# Large_Digit_Shield.net
KiCad netlist of a schematic drawn in EAGLE
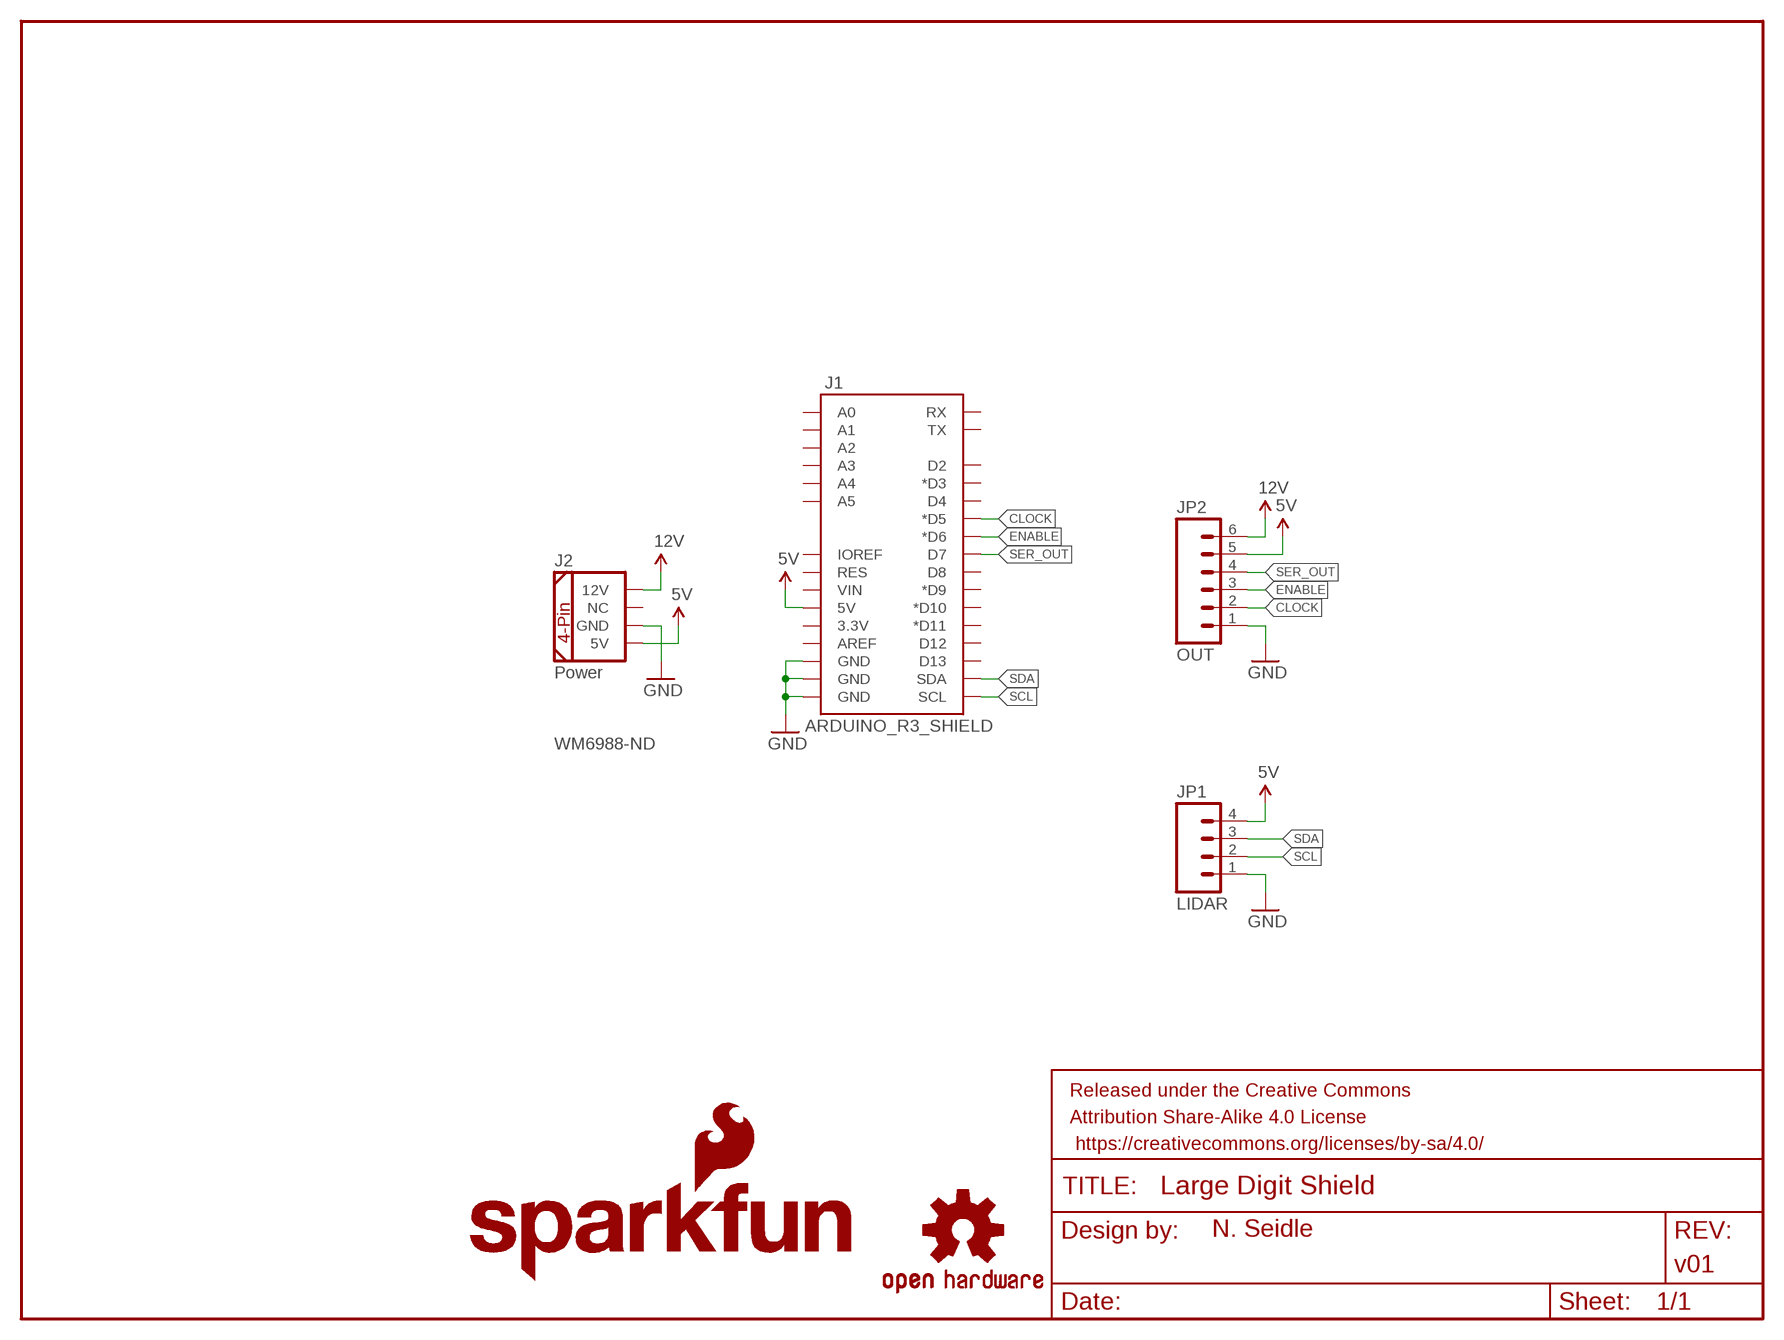
[diagram p0: schematic, sheet 1]

(export (version "E")
  (design (tool "Eeschema 10.0.6"))
  (components
    (comp (ref "FRAME1")
      (value "FRAME-LETTER")
      (footprint "eagle-import:CREATIVE_COMMONS")
      (fields (field (name "DESIGNER") "N. Seidle"))
      (libsource (lib "eagle-import") (part "FRAME-LETTER"))
    )
    (comp (ref "J1")
      (value "ARDUINO_R3_SHIELD")
      (footprint "eagle-import:UNO_R3_SHIELD")
      (libsource (lib "eagle-import") (part "ARDUINO_R3_SHIELD"))
    )
    (comp (ref "J2")
      (value "Power")
      (footprint "eagle-import:COMPUTER-PERIPHERAL-POWER-RA")
      (libsource (lib "eagle-import") (part "COMPUTER-PERIPHERAL-POWERRA"))
    )
    (comp (ref "JP1")
      (value "LIDAR")
      (footprint "eagle-import:JST-4-PTH")
      (libsource (lib "eagle-import") (part "M04JST-PTH"))
    )
    (comp (ref "JP2")
      (value "OUT")
      (footprint "eagle-import:1X06")
      (libsource (lib "eagle-import") (part "M06SILK_FEMALE_PTH"))
    )
    (comp (ref "LOGO1")
      (value "SFE_LOGO_NAME_FLAME.2_INCH")
      (footprint "eagle-import:SFE_LOGO_NAME_FLAME_.2")
      (libsource (lib "eagle-import") (part "SFE_LOGO_NAME_FLAME.2_INCH"))
    )
    (comp (ref "LOGO2")
      (value "OSHW-LOGOS")
      (footprint "eagle-import:OSHW-LOGO-S")
      (libsource (lib "eagle-import") (part "OSHW-LOGOS"))
    )
  )
  (nets
    (net (code "1") (name "5V") (class "Default")
      (node (ref "J1") (pin "5V") (pinfunction "5V_5V") (pintype "bidirectional"))
      (node (ref "J2") (pin "5V") (pinfunction "5V_5V") (pintype "passive"))
      (node (ref "JP1") (pin "4") (pinfunction "4_4") (pintype "passive"))
      (node (ref "JP2") (pin "5") (pinfunction "5_5") (pintype "passive"))
    )
    (net (code "2") (name "12V") (class "Default")
      (node (ref "J2") (pin "12V") (pinfunction "12V_12V") (pintype "passive"))
      (node (ref "JP2") (pin "6") (pinfunction "6_6") (pintype "passive"))
    )
    (net (code "3") (name "CLOCK") (class "Default")
      (node (ref "J1") (pin "D5") (pinfunction "*D5_D5") (pintype "bidirectional"))
      (node (ref "JP2") (pin "2") (pinfunction "2_2") (pintype "passive"))
    )
    (net (code "4") (name "ENABLE") (class "Default")
      (node (ref "J1") (pin "D6") (pinfunction "*D6_D6") (pintype "bidirectional"))
      (node (ref "JP2") (pin "3") (pinfunction "3_3") (pintype "passive"))
    )
    (net (code "5") (name "GND") (class "Default")
      (node (ref "J1") (pin "GND@0") (pinfunction "GND_GND@0") (pintype "bidirectional"))
      (node (ref "J1") (pin "GND@1") (pinfunction "GND_GND@1") (pintype "bidirectional"))
      (node (ref "J1") (pin "GND@2") (pinfunction "GND_GND@2") (pintype "bidirectional"))
      (node (ref "J2") (pin "GND") (pinfunction "GND_GND") (pintype "passive"))
      (node (ref "JP1") (pin "1") (pinfunction "1_1") (pintype "passive"))
      (node (ref "JP2") (pin "1") (pinfunction "1_1") (pintype "passive"))
    )
    (net (code "6") (name "SCL") (class "Default")
      (node (ref "J1") (pin "SCL") (pinfunction "SCL_SCL") (pintype "bidirectional"))
      (node (ref "JP1") (pin "2") (pinfunction "2_2") (pintype "passive"))
    )
    (net (code "7") (name "SDA") (class "Default")
      (node (ref "J1") (pin "SDA") (pinfunction "SDA_SDA") (pintype "bidirectional"))
      (node (ref "JP1") (pin "3") (pinfunction "3_3") (pintype "passive"))
    )
    (net (code "8") (name "SER_OUT") (class "Default")
      (node (ref "J1") (pin "D7") (pinfunction "D7_D7") (pintype "bidirectional"))
      (node (ref "JP2") (pin "4") (pinfunction "4_4") (pintype "passive"))
    )
    (net (code "9") (name "unconnected-(J1-*D3-PadD3)") (class "Default")
      (node (ref "J1") (pin "D3") (pinfunction "*D3_D3") (pintype "bidirectional"))
    )
    (net (code "10") (name "unconnected-(J1-*D9-PadD9)") (class "Default")
      (node (ref "J1") (pin "D9") (pinfunction "*D9_D9") (pintype "bidirectional"))
    )
    (net (code "11") (name "unconnected-(J1-*D10-PadD10)") (class "Default")
      (node (ref "J1") (pin "D10") (pinfunction "*D10_D10") (pintype "bidirectional"))
    )
    (net (code "12") (name "unconnected-(J1-*D11-PadD11)") (class "Default")
      (node (ref "J1") (pin "D11") (pinfunction "*D11_D11") (pintype "bidirectional"))
    )
    (net (code "13") (name "unconnected-(J1-Pad3.3V)") (class "Default")
      (node (ref "J1") (pin "3.3V") (pinfunction "3.3V_3.3V") (pintype "bidirectional"))
    )
    (net (code "14") (name "unconnected-(J1-PadA0)") (class "Default")
      (node (ref "J1") (pin "A0") (pinfunction "A0_A0") (pintype "bidirectional"))
    )
    (net (code "15") (name "unconnected-(J1-PadA1)") (class "Default")
      (node (ref "J1") (pin "A1") (pinfunction "A1_A1") (pintype "bidirectional"))
    )
    (net (code "16") (name "unconnected-(J1-PadA2)") (class "Default")
      (node (ref "J1") (pin "A2") (pinfunction "A2_A2") (pintype "bidirectional"))
    )
    (net (code "17") (name "unconnected-(J1-PadA3)") (class "Default")
      (node (ref "J1") (pin "A3") (pinfunction "A3_A3") (pintype "bidirectional"))
    )
    (net (code "18") (name "unconnected-(J1-PadA4)") (class "Default")
      (node (ref "J1") (pin "A4") (pinfunction "A4_A4") (pintype "bidirectional"))
    )
    (net (code "19") (name "unconnected-(J1-PadA5)") (class "Default")
      (node (ref "J1") (pin "A5") (pinfunction "A5_A5") (pintype "bidirectional"))
    )
    (net (code "20") (name "unconnected-(J1-PadAREF)") (class "Default")
      (node (ref "J1") (pin "AREF") (pinfunction "AREF_AREF") (pintype "bidirectional"))
    )
    (net (code "21") (name "unconnected-(J1-PadD2)") (class "Default")
      (node (ref "J1") (pin "D2") (pinfunction "D2_D2") (pintype "bidirectional"))
    )
    (net (code "22") (name "unconnected-(J1-PadD4)") (class "Default")
      (node (ref "J1") (pin "D4") (pinfunction "D4_D4") (pintype "bidirectional"))
    )
    (net (code "23") (name "unconnected-(J1-PadD8)") (class "Default")
      (node (ref "J1") (pin "D8") (pinfunction "D8_D8") (pintype "bidirectional"))
    )
    (net (code "24") (name "unconnected-(J1-PadD12)") (class "Default")
      (node (ref "J1") (pin "D12") (pinfunction "D12_D12") (pintype "bidirectional"))
    )
    (net (code "25") (name "unconnected-(J1-PadD13)") (class "Default")
      (node (ref "J1") (pin "D13") (pinfunction "D13_D13") (pintype "bidirectional"))
    )
    (net (code "26") (name "unconnected-(J1-PadIOREF)") (class "Default")
      (node (ref "J1") (pin "IOREF") (pinfunction "IOREF_IOREF") (pintype "bidirectional"))
    )
    (net (code "27") (name "unconnected-(J1-PadRES)") (class "Default")
      (node (ref "J1") (pin "RES") (pinfunction "RES_RES") (pintype "bidirectional"))
    )
    (net (code "28") (name "unconnected-(J1-PadRX)") (class "Default")
      (node (ref "J1") (pin "RX") (pinfunction "RX_RX") (pintype "bidirectional"))
    )
    (net (code "29") (name "unconnected-(J1-PadTX)") (class "Default")
      (node (ref "J1") (pin "TX") (pinfunction "TX_TX") (pintype "bidirectional"))
    )
    (net (code "30") (name "unconnected-(J1-PadVIN)") (class "Default")
      (node (ref "J1") (pin "VIN") (pinfunction "VIN_VIN") (pintype "bidirectional"))
    )
    (net (code "31") (name "unconnected-(J2-PadNC)") (class "Default")
      (node (ref "J2") (pin "NC") (pinfunction "NC_NC") (pintype "passive"))
    )
  )
)
